# working.net
KiCad netlist of a schematic drawn in EAGLE
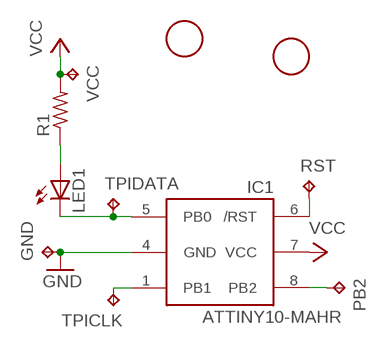
[diagram p0: schematic, sheet 1]

(export (version "E")
  (design (tool "Eeschema 10.0.6"))
  (components
    (comp (ref "GND")
      (value "TPTP10R")
      (footprint "eagle-import:TP10R")
      (libsource (lib "eagle-import") (part "TPTP10R"))
    )
    (comp (ref "IC1")
      (value "ATTINY10-MAHR")
      (footprint "eagle-import:UDFN-8")
      (libsource (lib "eagle-import") (part "ATTINY10-MAHR"))
    )
    (comp (ref "LED1")
      (value "LEDSMLK34")
      (footprint "eagle-import:SMLK34")
      (libsource (lib "eagle-import") (part "LEDSMLK34"))
    )
    (comp (ref "PB2")
      (value "TPTP10R")
      (footprint "eagle-import:TP10R")
      (libsource (lib "eagle-import") (part "TPTP10R"))
    )
    (comp (ref "R1")
      (value "R-US_R0805")
      (footprint "eagle-import:R0805")
      (libsource (lib "eagle-import") (part "R-US_R0805"))
    )
    (comp (ref "RST")
      (value "TPTP10R")
      (footprint "eagle-import:TP10R")
      (libsource (lib "eagle-import") (part "TPTP10R"))
    )
    (comp (ref "TPICLK")
      (value "TPTP10R")
      (footprint "eagle-import:TP10R")
      (libsource (lib "eagle-import") (part "TPTP10R"))
    )
    (comp (ref "TPIDATA")
      (value "TPTP10R")
      (footprint "eagle-import:TP10R")
      (libsource (lib "eagle-import") (part "TPTP10R"))
    )
    (comp (ref "U$2")
      (value "FIDUCIAL")
      (footprint "eagle-import:FIDUCIAL_1MM")
      (libsource (lib "eagle-import") (part "FIDUCIAL"))
    )
    (comp (ref "U$3")
      (value "FIDUCIAL")
      (footprint "eagle-import:FIDUCIAL_1MM")
      (libsource (lib "eagle-import") (part "FIDUCIAL"))
    )
    (comp (ref "VCC")
      (value "TPTP10R")
      (footprint "eagle-import:TP10R")
      (libsource (lib "eagle-import") (part "TPTP10R"))
    )
  )
  (nets
    (net (code "1") (name "GND") (class "Default")
      (node (ref "GND") (pin "TP") (pinfunction "TP_TP") (pintype "input"))
      (node (ref "IC1") (pin "4") (pinfunction "GND_4") (pintype "power_in"))
    )
    (net (code "2") (name "Net-(IC1-PB0)") (class "Default")
      (node (ref "IC1") (pin "5") (pinfunction "PB0_5") (pintype "bidirectional"))
      (node (ref "LED1") (pin "K") (pinfunction "C_K") (pintype "passive"))
      (node (ref "TPIDATA") (pin "TP") (pinfunction "TP_TP") (pintype "input"))
    )
    (net (code "3") (name "Net-(IC1-PB1)") (class "Default")
      (node (ref "IC1") (pin "1") (pinfunction "PB1_1") (pintype "bidirectional"))
      (node (ref "TPICLK") (pin "TP") (pinfunction "TP_TP") (pintype "input"))
    )
    (net (code "4") (name "Net-(IC1-PB2)") (class "Default")
      (node (ref "IC1") (pin "8") (pinfunction "PB2_8") (pintype "bidirectional"))
      (node (ref "PB2") (pin "TP") (pinfunction "TP_TP") (pintype "input"))
    )
    (net (code "5") (name "Net-(IC1-{slash}RST)") (class "Default")
      (node (ref "IC1") (pin "6") (pinfunction "/RST_6") (pintype "bidirectional"))
      (node (ref "RST") (pin "TP") (pinfunction "TP_TP") (pintype "input"))
    )
    (net (code "6") (name "Net-(LED1-PadA)") (class "Default")
      (node (ref "LED1") (pin "A") (pinfunction "A_A") (pintype "passive"))
      (node (ref "R1") (pin "1") (pinfunction "1_1") (pintype "passive"))
    )
    (net (code "7") (name "VCC") (class "Default")
      (node (ref "IC1") (pin "7") (pinfunction "VCC_7") (pintype "power_in"))
      (node (ref "R1") (pin "2") (pinfunction "2_2") (pintype "passive"))
      (node (ref "VCC") (pin "TP") (pinfunction "TP_TP") (pintype "input"))
    )
  )
)
